# LEDSubMatrixLowDensityTHT.net
KiCad netlist of a schematic drawn in EAGLE
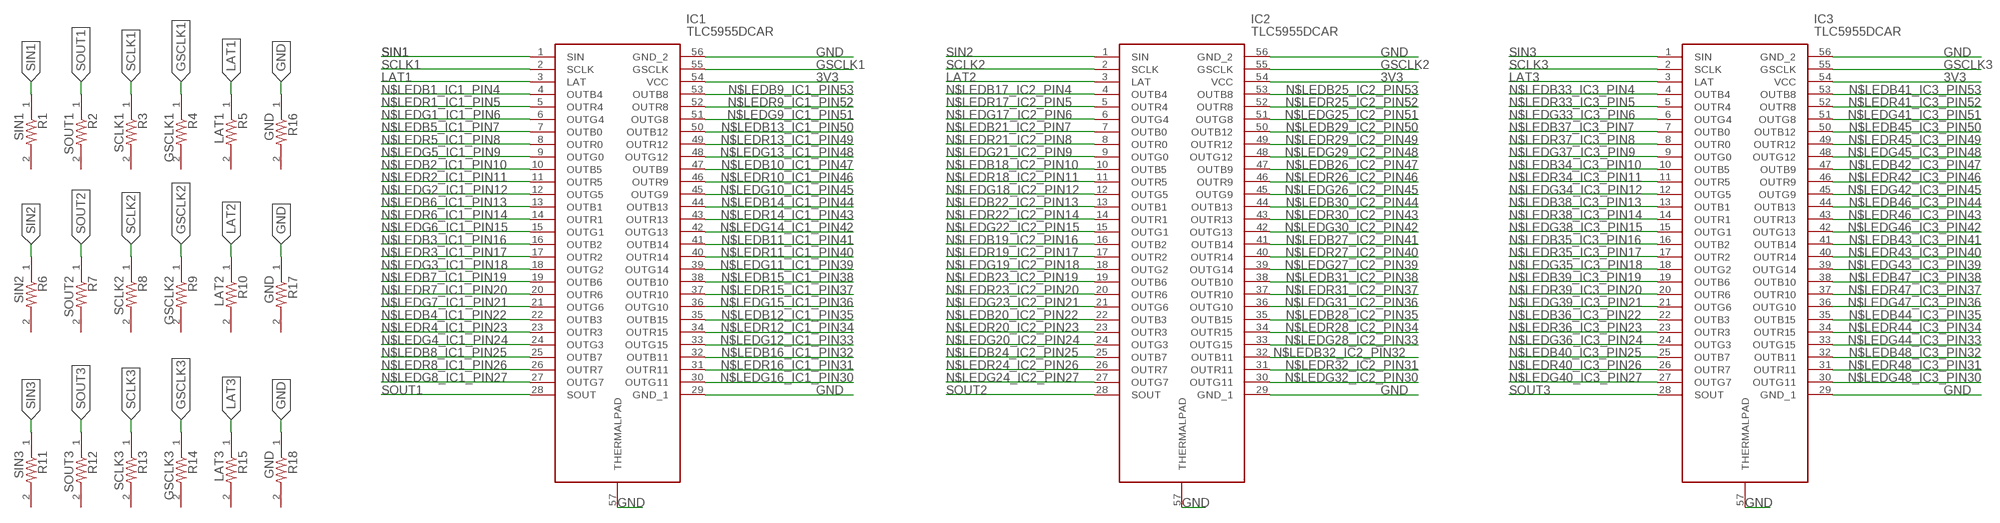
[diagram p0: schematic, sheet 1, part 1 of 2]
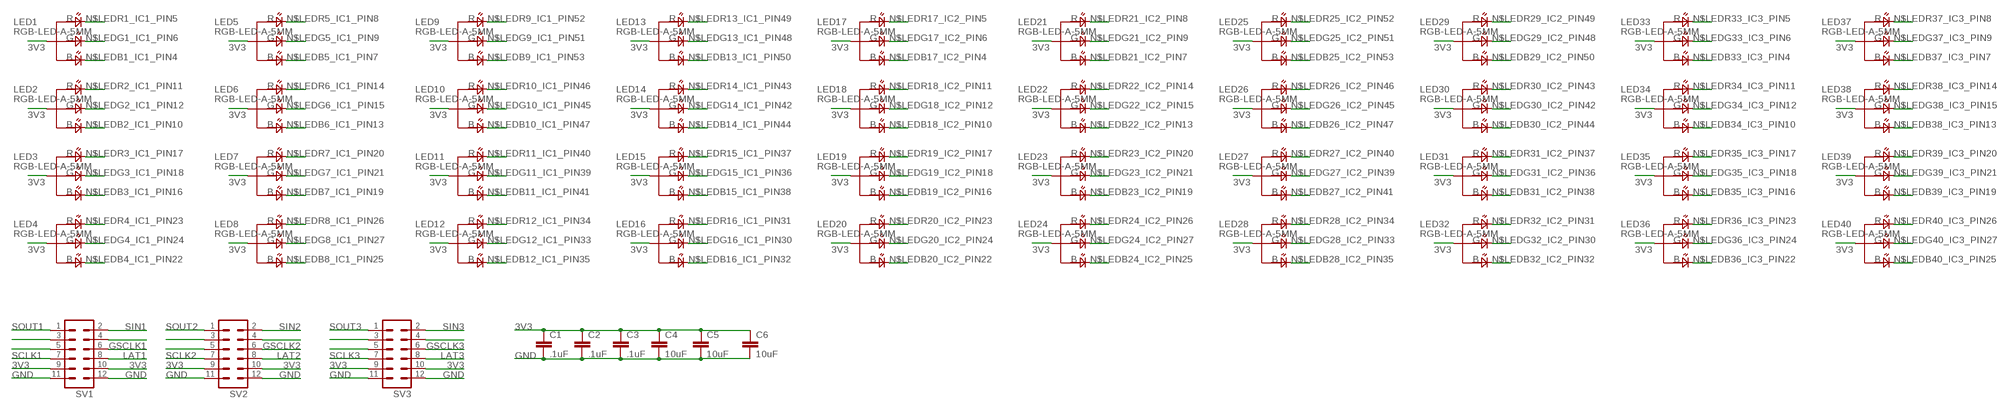
[diagram p1: schematic, sheet 1, part 2 of 2]

(export (version "E")
  (design (tool "Eeschema 10.0.6"))
  (components
    (comp (ref "C1")
      (value ".1uF")
      (footprint "eagle-import:C0603")
      (libsource (lib "eagle-import") (part "C-EUC0603"))
    )
    (comp (ref "C2")
      (value ".1uF")
      (footprint "eagle-import:C0603")
      (libsource (lib "eagle-import") (part "C-EUC0603"))
    )
    (comp (ref "C3")
      (value ".1uF")
      (footprint "eagle-import:C0603")
      (libsource (lib "eagle-import") (part "C-EUC0603"))
    )
    (comp (ref "C4")
      (value "10uF")
      (footprint "eagle-import:C0805")
      (libsource (lib "eagle-import") (part "C-EUC0805"))
    )
    (comp (ref "C5")
      (value "10uF")
      (footprint "eagle-import:C0805")
      (libsource (lib "eagle-import") (part "C-EUC0805"))
    )
    (comp (ref "C6")
      (value "10uF")
      (footprint "eagle-import:C0805")
      (libsource (lib "eagle-import") (part "C-EUC0805"))
    )
    (comp (ref "IC1")
      (value "TLC5955DCAR")
      (footprint "eagle-import:SOP50P810X120-57N")
      (fields (field (name "MOUSER_PART_NUMBER") "595-TLC5955DCAR"))
      (libsource (lib "eagle-import") (part "TLC5955DCAR"))
    )
    (comp (ref "IC2")
      (value "TLC5955DCAR")
      (footprint "eagle-import:SOP50P810X120-57N")
      (fields (field (name "MOUSER_PART_NUMBER") "595-TLC5955DCAR"))
      (libsource (lib "eagle-import") (part "TLC5955DCAR"))
    )
    (comp (ref "IC3")
      (value "TLC5955DCAR")
      (footprint "eagle-import:SOP50P810X120-57N")
      (fields (field (name "MOUSER_PART_NUMBER") "595-TLC5955DCAR"))
      (libsource (lib "eagle-import") (part "TLC5955DCAR"))
    )
    (comp (ref "LED1")
      (value "RGB-LED-A-5MM")
      (footprint "eagle-import:RGBLED-A-5MM")
      (libsource (lib "eagle-import") (part "RGB-LED-A-5MM"))
    )
    (comp (ref "LED2")
      (value "RGB-LED-A-5MM")
      (footprint "eagle-import:RGBLED-A-5MM")
      (libsource (lib "eagle-import") (part "RGB-LED-A-5MM"))
    )
    (comp (ref "LED3")
      (value "RGB-LED-A-5MM")
      (footprint "eagle-import:RGBLED-A-5MM")
      (libsource (lib "eagle-import") (part "RGB-LED-A-5MM"))
    )
    (comp (ref "LED4")
      (value "RGB-LED-A-5MM")
      (footprint "eagle-import:RGBLED-A-5MM")
      (libsource (lib "eagle-import") (part "RGB-LED-A-5MM"))
    )
    (comp (ref "LED5")
      (value "RGB-LED-A-5MM")
      (footprint "eagle-import:RGBLED-A-5MM")
      (libsource (lib "eagle-import") (part "RGB-LED-A-5MM"))
    )
    (comp (ref "LED6")
      (value "RGB-LED-A-5MM")
      (footprint "eagle-import:RGBLED-A-5MM")
      (libsource (lib "eagle-import") (part "RGB-LED-A-5MM"))
    )
    (comp (ref "LED7")
      (value "RGB-LED-A-5MM")
      (footprint "eagle-import:RGBLED-A-5MM")
      (libsource (lib "eagle-import") (part "RGB-LED-A-5MM"))
    )
    (comp (ref "LED8")
      (value "RGB-LED-A-5MM")
      (footprint "eagle-import:RGBLED-A-5MM")
      (libsource (lib "eagle-import") (part "RGB-LED-A-5MM"))
    )
    (comp (ref "LED9")
      (value "RGB-LED-A-5MM")
      (footprint "eagle-import:RGBLED-A-5MM")
      (libsource (lib "eagle-import") (part "RGB-LED-A-5MM"))
    )
    (comp (ref "LED10")
      (value "RGB-LED-A-5MM")
      (footprint "eagle-import:RGBLED-A-5MM")
      (libsource (lib "eagle-import") (part "RGB-LED-A-5MM"))
    )
    (comp (ref "LED11")
      (value "RGB-LED-A-5MM")
      (footprint "eagle-import:RGBLED-A-5MM")
      (libsource (lib "eagle-import") (part "RGB-LED-A-5MM"))
    )
    (comp (ref "LED12")
      (value "RGB-LED-A-5MM")
      (footprint "eagle-import:RGBLED-A-5MM")
      (libsource (lib "eagle-import") (part "RGB-LED-A-5MM"))
    )
    (comp (ref "LED13")
      (value "RGB-LED-A-5MM")
      (footprint "eagle-import:RGBLED-A-5MM")
      (libsource (lib "eagle-import") (part "RGB-LED-A-5MM"))
    )
    (comp (ref "LED14")
      (value "RGB-LED-A-5MM")
      (footprint "eagle-import:RGBLED-A-5MM")
      (libsource (lib "eagle-import") (part "RGB-LED-A-5MM"))
    )
    (comp (ref "LED15")
      (value "RGB-LED-A-5MM")
      (footprint "eagle-import:RGBLED-A-5MM")
      (libsource (lib "eagle-import") (part "RGB-LED-A-5MM"))
    )
    (comp (ref "LED16")
      (value "RGB-LED-A-5MM")
      (footprint "eagle-import:RGBLED-A-5MM")
      (libsource (lib "eagle-import") (part "RGB-LED-A-5MM"))
    )
    (comp (ref "LED17")
      (value "RGB-LED-A-5MM")
      (footprint "eagle-import:RGBLED-A-5MM")
      (libsource (lib "eagle-import") (part "RGB-LED-A-5MM"))
    )
    (comp (ref "LED18")
      (value "RGB-LED-A-5MM")
      (footprint "eagle-import:RGBLED-A-5MM")
      (libsource (lib "eagle-import") (part "RGB-LED-A-5MM"))
    )
    (comp (ref "LED19")
      (value "RGB-LED-A-5MM")
      (footprint "eagle-import:RGBLED-A-5MM")
      (libsource (lib "eagle-import") (part "RGB-LED-A-5MM"))
    )
    (comp (ref "LED20")
      (value "RGB-LED-A-5MM")
      (footprint "eagle-import:RGBLED-A-5MM")
      (libsource (lib "eagle-import") (part "RGB-LED-A-5MM"))
    )
    (comp (ref "LED21")
      (value "RGB-LED-A-5MM")
      (footprint "eagle-import:RGBLED-A-5MM")
      (libsource (lib "eagle-import") (part "RGB-LED-A-5MM"))
    )
    (comp (ref "LED22")
      (value "RGB-LED-A-5MM")
      (footprint "eagle-import:RGBLED-A-5MM")
      (libsource (lib "eagle-import") (part "RGB-LED-A-5MM"))
    )
    (comp (ref "LED23")
      (value "RGB-LED-A-5MM")
      (footprint "eagle-import:RGBLED-A-5MM")
      (libsource (lib "eagle-import") (part "RGB-LED-A-5MM"))
    )
    (comp (ref "LED24")
      (value "RGB-LED-A-5MM")
      (footprint "eagle-import:RGBLED-A-5MM")
      (libsource (lib "eagle-import") (part "RGB-LED-A-5MM"))
    )
    (comp (ref "LED25")
      (value "RGB-LED-A-5MM")
      (footprint "eagle-import:RGBLED-A-5MM")
      (libsource (lib "eagle-import") (part "RGB-LED-A-5MM"))
    )
    (comp (ref "LED26")
      (value "RGB-LED-A-5MM")
      (footprint "eagle-import:RGBLED-A-5MM")
      (libsource (lib "eagle-import") (part "RGB-LED-A-5MM"))
    )
    (comp (ref "LED27")
      (value "RGB-LED-A-5MM")
      (footprint "eagle-import:RGBLED-A-5MM")
      (libsource (lib "eagle-import") (part "RGB-LED-A-5MM"))
    )
    (comp (ref "LED28")
      (value "RGB-LED-A-5MM")
      (footprint "eagle-import:RGBLED-A-5MM")
      (libsource (lib "eagle-import") (part "RGB-LED-A-5MM"))
    )
    (comp (ref "LED29")
      (value "RGB-LED-A-5MM")
      (footprint "eagle-import:RGBLED-A-5MM")
      (libsource (lib "eagle-import") (part "RGB-LED-A-5MM"))
    )
    (comp (ref "LED30")
      (value "RGB-LED-A-5MM")
      (footprint "eagle-import:RGBLED-A-5MM")
      (libsource (lib "eagle-import") (part "RGB-LED-A-5MM"))
    )
    (comp (ref "LED31")
      (value "RGB-LED-A-5MM")
      (footprint "eagle-import:RGBLED-A-5MM")
      (libsource (lib "eagle-import") (part "RGB-LED-A-5MM"))
    )
    (comp (ref "LED32")
      (value "RGB-LED-A-5MM")
      (footprint "eagle-import:RGBLED-A-5MM")
      (libsource (lib "eagle-import") (part "RGB-LED-A-5MM"))
    )
    (comp (ref "LED33")
      (value "RGB-LED-A-5MM")
      (footprint "eagle-import:RGBLED-A-5MM")
      (libsource (lib "eagle-import") (part "RGB-LED-A-5MM"))
    )
    (comp (ref "LED34")
      (value "RGB-LED-A-5MM")
      (footprint "eagle-import:RGBLED-A-5MM")
      (libsource (lib "eagle-import") (part "RGB-LED-A-5MM"))
    )
    (comp (ref "LED35")
      (value "RGB-LED-A-5MM")
      (footprint "eagle-import:RGBLED-A-5MM")
      (libsource (lib "eagle-import") (part "RGB-LED-A-5MM"))
    )
    (comp (ref "LED36")
      (value "RGB-LED-A-5MM")
      (footprint "eagle-import:RGBLED-A-5MM")
      (libsource (lib "eagle-import") (part "RGB-LED-A-5MM"))
    )
    (comp (ref "LED37")
      (value "RGB-LED-A-5MM")
      (footprint "eagle-import:RGBLED-A-5MM")
      (libsource (lib "eagle-import") (part "RGB-LED-A-5MM"))
    )
    (comp (ref "LED38")
      (value "RGB-LED-A-5MM")
      (footprint "eagle-import:RGBLED-A-5MM")
      (libsource (lib "eagle-import") (part "RGB-LED-A-5MM"))
    )
    (comp (ref "LED39")
      (value "RGB-LED-A-5MM")
      (footprint "eagle-import:RGBLED-A-5MM")
      (libsource (lib "eagle-import") (part "RGB-LED-A-5MM"))
    )
    (comp (ref "LED40")
      (value "RGB-LED-A-5MM")
      (footprint "eagle-import:RGBLED-A-5MM")
      (libsource (lib "eagle-import") (part "RGB-LED-A-5MM"))
    )
    (comp (ref "R1")
      (value "SIN1")
      (footprint "eagle-import:RESC3216X70N")
      (fields
        (field (name "DIGI-KEY_PART_NUMBER") "2019-RCWCTECT-ND")
        (field (name "MF") "KOA Speer")
        (field (name "MP") "RCWCTE")
      )
      (libsource (lib "eagle-import") (part "RCWCTE"))
    )
    (comp (ref "R2")
      (value "SOUT1")
      (footprint "eagle-import:RESC3216X70N")
      (fields
        (field (name "DIGI-KEY_PART_NUMBER") "2019-RCWCTECT-ND")
        (field (name "MF") "KOA Speer")
        (field (name "MP") "RCWCTE")
      )
      (libsource (lib "eagle-import") (part "RCWCTE"))
    )
    (comp (ref "R3")
      (value "SCLK1")
      (footprint "eagle-import:RESC3216X70N")
      (fields
        (field (name "DIGI-KEY_PART_NUMBER") "2019-RCWCTECT-ND")
        (field (name "MF") "KOA Speer")
        (field (name "MP") "RCWCTE")
      )
      (libsource (lib "eagle-import") (part "RCWCTE"))
    )
    (comp (ref "R4")
      (value "GSCLK1")
      (footprint "eagle-import:RESC3216X70N")
      (fields
        (field (name "DIGI-KEY_PART_NUMBER") "2019-RCWCTECT-ND")
        (field (name "MF") "KOA Speer")
        (field (name "MP") "RCWCTE")
      )
      (libsource (lib "eagle-import") (part "RCWCTE"))
    )
    (comp (ref "R5")
      (value "LAT1")
      (footprint "eagle-import:RESC3216X70N")
      (fields
        (field (name "DIGI-KEY_PART_NUMBER") "2019-RCWCTECT-ND")
        (field (name "MF") "KOA Speer")
        (field (name "MP") "RCWCTE")
      )
      (libsource (lib "eagle-import") (part "RCWCTE"))
    )
    (comp (ref "R6")
      (value "SIN2")
      (footprint "eagle-import:RESC3216X70N")
      (fields
        (field (name "DIGI-KEY_PART_NUMBER") "2019-RCWCTECT-ND")
        (field (name "MF") "KOA Speer")
        (field (name "MP") "RCWCTE")
      )
      (libsource (lib "eagle-import") (part "RCWCTE"))
    )
    (comp (ref "R7")
      (value "SOUT2")
      (footprint "eagle-import:RESC3216X70N")
      (fields
        (field (name "DIGI-KEY_PART_NUMBER") "2019-RCWCTECT-ND")
        (field (name "MF") "KOA Speer")
        (field (name "MP") "RCWCTE")
      )
      (libsource (lib "eagle-import") (part "RCWCTE"))
    )
    (comp (ref "R8")
      (value "SCLK2")
      (footprint "eagle-import:RESC3216X70N")
      (fields
        (field (name "DIGI-KEY_PART_NUMBER") "2019-RCWCTECT-ND")
        (field (name "MF") "KOA Speer")
        (field (name "MP") "RCWCTE")
      )
      (libsource (lib "eagle-import") (part "RCWCTE"))
    )
    (comp (ref "R9")
      (value "GSCLK2")
      (footprint "eagle-import:RESC3216X70N")
      (fields
        (field (name "DIGI-KEY_PART_NUMBER") "2019-RCWCTECT-ND")
        (field (name "MF") "KOA Speer")
        (field (name "MP") "RCWCTE")
      )
      (libsource (lib "eagle-import") (part "RCWCTE"))
    )
    (comp (ref "R10")
      (value "LAT2")
      (footprint "eagle-import:RESC3216X70N")
      (fields
        (field (name "DIGI-KEY_PART_NUMBER") "2019-RCWCTECT-ND")
        (field (name "MF") "KOA Speer")
        (field (name "MP") "RCWCTE")
      )
      (libsource (lib "eagle-import") (part "RCWCTE"))
    )
    (comp (ref "R11")
      (value "SIN3")
      (footprint "eagle-import:RESC3216X70N")
      (fields
        (field (name "DIGI-KEY_PART_NUMBER") "2019-RCWCTECT-ND")
        (field (name "MF") "KOA Speer")
        (field (name "MP") "RCWCTE")
      )
      (libsource (lib "eagle-import") (part "RCWCTE"))
    )
    (comp (ref "R12")
      (value "SOUT3")
      (footprint "eagle-import:RESC3216X70N")
      (fields
        (field (name "DIGI-KEY_PART_NUMBER") "2019-RCWCTECT-ND")
        (field (name "MF") "KOA Speer")
        (field (name "MP") "RCWCTE")
      )
      (libsource (lib "eagle-import") (part "RCWCTE"))
    )
    (comp (ref "R13")
      (value "SCLK3")
      (footprint "eagle-import:RESC3216X70N")
      (fields
        (field (name "DIGI-KEY_PART_NUMBER") "2019-RCWCTECT-ND")
        (field (name "MF") "KOA Speer")
        (field (name "MP") "RCWCTE")
      )
      (libsource (lib "eagle-import") (part "RCWCTE"))
    )
    (comp (ref "R14")
      (value "GSCLK3")
      (footprint "eagle-import:RESC3216X70N")
      (fields
        (field (name "DIGI-KEY_PART_NUMBER") "2019-RCWCTECT-ND")
        (field (name "MF") "KOA Speer")
        (field (name "MP") "RCWCTE")
      )
      (libsource (lib "eagle-import") (part "RCWCTE"))
    )
    (comp (ref "R15")
      (value "LAT3")
      (footprint "eagle-import:RESC3216X70N")
      (fields
        (field (name "DIGI-KEY_PART_NUMBER") "2019-RCWCTECT-ND")
        (field (name "MF") "KOA Speer")
        (field (name "MP") "RCWCTE")
      )
      (libsource (lib "eagle-import") (part "RCWCTE"))
    )
    (comp (ref "R16")
      (value "GND")
      (footprint "eagle-import:RESC3216X70N")
      (fields
        (field (name "DIGI-KEY_PART_NUMBER") "2019-RCWCTECT-ND")
        (field (name "MF") "KOA Speer")
        (field (name "MP") "RCWCTE")
      )
      (libsource (lib "eagle-import") (part "RCWCTE"))
    )
    (comp (ref "R17")
      (value "GND")
      (footprint "eagle-import:RESC3216X70N")
      (fields
        (field (name "DIGI-KEY_PART_NUMBER") "2019-RCWCTECT-ND")
        (field (name "MF") "KOA Speer")
        (field (name "MP") "RCWCTE")
      )
      (libsource (lib "eagle-import") (part "RCWCTE"))
    )
    (comp (ref "R18")
      (value "GND")
      (footprint "eagle-import:RESC3216X70N")
      (fields
        (field (name "DIGI-KEY_PART_NUMBER") "2019-RCWCTECT-ND")
        (field (name "MF") "KOA Speer")
        (field (name "MP") "RCWCTE")
      )
      (libsource (lib "eagle-import") (part "RCWCTE"))
    )
    (comp (ref "SV1")
      (value "MA06-2")
      (footprint "eagle-import:MA06-2")
      (libsource (lib "eagle-import") (part "MA06-2"))
    )
    (comp (ref "SV2")
      (value "MA06-2")
      (footprint "eagle-import:MA06-2")
      (libsource (lib "eagle-import") (part "MA06-2"))
    )
    (comp (ref "SV3")
      (value "MA06-2")
      (footprint "eagle-import:MA06-2")
      (libsource (lib "eagle-import") (part "MA06-2"))
    )
  )
  (nets
    (net (code "1") (name "/3V3") (class "Default")
      (node (ref "C1") (pin "1") (pinfunction "1_1") (pintype "passive"))
      (node (ref "C2") (pin "1") (pinfunction "1_1") (pintype "passive"))
      (node (ref "C3") (pin "1") (pinfunction "1_1") (pintype "passive"))
      (node (ref "C4") (pin "1") (pinfunction "1_1") (pintype "passive"))
      (node (ref "C5") (pin "1") (pinfunction "1_1") (pintype "passive"))
      (node (ref "C6") (pin "1") (pinfunction "1_1") (pintype "passive"))
      (node (ref "IC1") (pin "54") (pinfunction "VCC_54") (pintype "bidirectional"))
      (node (ref "IC2") (pin "54") (pinfunction "VCC_54") (pintype "bidirectional"))
      (node (ref "IC3") (pin "54") (pinfunction "VCC_54") (pintype "bidirectional"))
      (node (ref "LED1") (pin "AN") (pinfunction "COM_AN") (pintype "bidirectional"))
      (node (ref "LED10") (pin "AN") (pinfunction "COM_AN") (pintype "bidirectional"))
      (node (ref "LED11") (pin "AN") (pinfunction "COM_AN") (pintype "bidirectional"))
      (node (ref "LED12") (pin "AN") (pinfunction "COM_AN") (pintype "bidirectional"))
      (node (ref "LED13") (pin "AN") (pinfunction "COM_AN") (pintype "bidirectional"))
      (node (ref "LED14") (pin "AN") (pinfunction "COM_AN") (pintype "bidirectional"))
      (node (ref "LED15") (pin "AN") (pinfunction "COM_AN") (pintype "bidirectional"))
      (node (ref "LED16") (pin "AN") (pinfunction "COM_AN") (pintype "bidirectional"))
      (node (ref "LED17") (pin "AN") (pinfunction "COM_AN") (pintype "bidirectional"))
      (node (ref "LED18") (pin "AN") (pinfunction "COM_AN") (pintype "bidirectional"))
      (node (ref "LED19") (pin "AN") (pinfunction "COM_AN") (pintype "bidirectional"))
      (node (ref "LED2") (pin "AN") (pinfunction "COM_AN") (pintype "bidirectional"))
      (node (ref "LED20") (pin "AN") (pinfunction "COM_AN") (pintype "bidirectional"))
      (node (ref "LED21") (pin "AN") (pinfunction "COM_AN") (pintype "bidirectional"))
      (node (ref "LED22") (pin "AN") (pinfunction "COM_AN") (pintype "bidirectional"))
      (node (ref "LED23") (pin "AN") (pinfunction "COM_AN") (pintype "bidirectional"))
      (node (ref "LED24") (pin "AN") (pinfunction "COM_AN") (pintype "bidirectional"))
      (node (ref "LED25") (pin "AN") (pinfunction "COM_AN") (pintype "bidirectional"))
      (node (ref "LED26") (pin "AN") (pinfunction "COM_AN") (pintype "bidirectional"))
      (node (ref "LED27") (pin "AN") (pinfunction "COM_AN") (pintype "bidirectional"))
      (node (ref "LED28") (pin "AN") (pinfunction "COM_AN") (pintype "bidirectional"))
      (node (ref "LED29") (pin "AN") (pinfunction "COM_AN") (pintype "bidirectional"))
      (node (ref "LED3") (pin "AN") (pinfunction "COM_AN") (pintype "bidirectional"))
      (node (ref "LED30") (pin "AN") (pinfunction "COM_AN") (pintype "bidirectional"))
      (node (ref "LED31") (pin "AN") (pinfunction "COM_AN") (pintype "bidirectional"))
      (node (ref "LED32") (pin "AN") (pinfunction "COM_AN") (pintype "bidirectional"))
      (node (ref "LED33") (pin "AN") (pinfunction "COM_AN") (pintype "bidirectional"))
      (node (ref "LED34") (pin "AN") (pinfunction "COM_AN") (pintype "bidirectional"))
      (node (ref "LED35") (pin "AN") (pinfunction "COM_AN") (pintype "bidirectional"))
      (node (ref "LED36") (pin "AN") (pinfunction "COM_AN") (pintype "bidirectional"))
      (node (ref "LED37") (pin "AN") (pinfunction "COM_AN") (pintype "bidirectional"))
      (node (ref "LED38") (pin "AN") (pinfunction "COM_AN") (pintype "bidirectional"))
      (node (ref "LED39") (pin "AN") (pinfunction "COM_AN") (pintype "bidirectional"))
      (node (ref "LED4") (pin "AN") (pinfunction "COM_AN") (pintype "bidirectional"))
      (node (ref "LED40") (pin "AN") (pinfunction "COM_AN") (pintype "bidirectional"))
      (node (ref "LED5") (pin "AN") (pinfunction "COM_AN") (pintype "bidirectional"))
      (node (ref "LED6") (pin "AN") (pinfunction "COM_AN") (pintype "bidirectional"))
      (node (ref "LED7") (pin "AN") (pinfunction "COM_AN") (pintype "bidirectional"))
      (node (ref "LED8") (pin "AN") (pinfunction "COM_AN") (pintype "bidirectional"))
      (node (ref "LED9") (pin "AN") (pinfunction "COM_AN") (pintype "bidirectional"))
      (node (ref "SV1") (pin "10") (pinfunction "10_10") (pintype "passive"))
      (node (ref "SV1") (pin "9") (pinfunction "9_9") (pintype "passive"))
      (node (ref "SV2") (pin "10") (pinfunction "10_10") (pintype "passive"))
      (node (ref "SV2") (pin "9") (pinfunction "9_9") (pintype "passive"))
      (node (ref "SV3") (pin "10") (pinfunction "10_10") (pintype "passive"))
      (node (ref "SV3") (pin "9") (pinfunction "9_9") (pintype "passive"))
    )
    (net (code "2") (name "/N$LEDB1_IC1_PIN4") (class "Default")
      (node (ref "IC1") (pin "4") (pinfunction "OUTB4_4") (pintype "bidirectional"))
      (node (ref "LED1") (pin "B") (pinfunction "BLUE_B") (pintype "bidirectional"))
    )
    (net (code "3") (name "/N$LEDB2_IC1_PIN10") (class "Default")
      (node (ref "IC1") (pin "10") (pinfunction "OUTB5_10") (pintype "bidirectional"))
      (node (ref "LED2") (pin "B") (pinfunction "BLUE_B") (pintype "bidirectional"))
    )
    (net (code "4") (name "/N$LEDB3_IC1_PIN16") (class "Default")
      (node (ref "IC1") (pin "16") (pinfunction "OUTB2_16") (pintype "bidirectional"))
      (node (ref "LED3") (pin "B") (pinfunction "BLUE_B") (pintype "bidirectional"))
    )
    (net (code "5") (name "/N$LEDB4_IC1_PIN22") (class "Default")
      (node (ref "IC1") (pin "22") (pinfunction "OUTB3_22") (pintype "bidirectional"))
      (node (ref "LED4") (pin "B") (pinfunction "BLUE_B") (pintype "bidirectional"))
    )
    (net (code "6") (name "/N$LEDB5_IC1_PIN7") (class "Default")
      (node (ref "IC1") (pin "7") (pinfunction "OUTB0_7") (pintype "bidirectional"))
      (node (ref "LED5") (pin "B") (pinfunction "BLUE_B") (pintype "bidirectional"))
    )
    (net (code "7") (name "/N$LEDB6_IC1_PIN13") (class "Default")
      (node (ref "IC1") (pin "13") (pinfunction "OUTB1_13") (pintype "bidirectional"))
      (node (ref "LED6") (pin "B") (pinfunction "BLUE_B") (pintype "bidirectional"))
    )
    (net (code "8") (name "/N$LEDB7_IC1_PIN19") (class "Default")
      (node (ref "IC1") (pin "19") (pinfunction "OUTB6_19") (pintype "bidirectional"))
      (node (ref "LED7") (pin "B") (pinfunction "BLUE_B") (pintype "bidirectional"))
    )
    (net (code "9") (name "/N$LEDB8_IC1_PIN25") (class "Default")
      (node (ref "IC1") (pin "25") (pinfunction "OUTB7_25") (pintype "bidirectional"))
      (node (ref "LED8") (pin "B") (pinfunction "BLUE_B") (pintype "bidirectional"))
    )
    (net (code "10") (name "/N$LEDB9_IC1_PIN53") (class "Default")
      (node (ref "IC1") (pin "53") (pinfunction "OUTB8_53") (pintype "bidirectional"))
      (node (ref "LED9") (pin "B") (pinfunction "BLUE_B") (pintype "bidirectional"))
    )
    (net (code "11") (name "/N$LEDB10_IC1_PIN47") (class "Default")
      (node (ref "IC1") (pin "47") (pinfunction "OUTB9_47") (pintype "bidirectional"))
      (node (ref "LED10") (pin "B") (pinfunction "BLUE_B") (pintype "bidirectional"))
    )
    (net (code "12") (name "/N$LEDB11_IC1_PIN41") (class "Default")
      (node (ref "IC1") (pin "41") (pinfunction "OUTB14_41") (pintype "bidirectional"))
      (node (ref "LED11") (pin "B") (pinfunction "BLUE_B") (pintype "bidirectional"))
    )
    (net (code "13") (name "/N$LEDB12_IC1_PIN35") (class "Default")
      (node (ref "IC1") (pin "35") (pinfunction "OUTB15_35") (pintype "bidirectional"))
      (node (ref "LED12") (pin "B") (pinfunction "BLUE_B") (pintype "bidirectional"))
    )
    (net (code "14") (name "/N$LEDB13_IC1_PIN50") (class "Default")
      (node (ref "IC1") (pin "50") (pinfunction "OUTB12_50") (pintype "bidirectional"))
      (node (ref "LED13") (pin "B") (pinfunction "BLUE_B") (pintype "bidirectional"))
    )
    (net (code "15") (name "/N$LEDB14_IC1_PIN44") (class "Default")
      (node (ref "IC1") (pin "44") (pinfunction "OUTB13_44") (pintype "bidirectional"))
      (node (ref "LED14") (pin "B") (pinfunction "BLUE_B") (pintype "bidirectional"))
    )
    (net (code "16") (name "/N$LEDB15_IC1_PIN38") (class "Default")
      (node (ref "IC1") (pin "38") (pinfunction "OUTB10_38") (pintype "bidirectional"))
      (node (ref "LED15") (pin "B") (pinfunction "BLUE_B") (pintype "bidirectional"))
    )
    (net (code "17") (name "/N$LEDB16_IC1_PIN32") (class "Default")
      (node (ref "IC1") (pin "32") (pinfunction "OUTB11_32") (pintype "bidirectional"))
      (node (ref "LED16") (pin "B") (pinfunction "BLUE_B") (pintype "bidirectional"))
    )
    (net (code "18") (name "/N$LEDB17_IC2_PIN4") (class "Default")
      (node (ref "IC2") (pin "4") (pinfunction "OUTB4_4") (pintype "bidirectional"))
      (node (ref "LED17") (pin "B") (pinfunction "BLUE_B") (pintype "bidirectional"))
    )
    (net (code "19") (name "/N$LEDB18_IC2_PIN10") (class "Default")
      (node (ref "IC2") (pin "10") (pinfunction "OUTB5_10") (pintype "bidirectional"))
      (node (ref "LED18") (pin "B") (pinfunction "BLUE_B") (pintype "bidirectional"))
    )
    (net (code "20") (name "/N$LEDB19_IC2_PIN16") (class "Default")
      (node (ref "IC2") (pin "16") (pinfunction "OUTB2_16") (pintype "bidirectional"))
      (node (ref "LED19") (pin "B") (pinfunction "BLUE_B") (pintype "bidirectional"))
    )
    (net (code "21") (name "/N$LEDB20_IC2_PIN22") (class "Default")
      (node (ref "IC2") (pin "22") (pinfunction "OUTB3_22") (pintype "bidirectional"))
      (node (ref "LED20") (pin "B") (pinfunction "BLUE_B") (pintype "bidirectional"))
    )
    (net (code "22") (name "/N$LEDB21_IC2_PIN7") (class "Default")
      (node (ref "IC2") (pin "7") (pinfunction "OUTB0_7") (pintype "bidirectional"))
      (node (ref "LED21") (pin "B") (pinfunction "BLUE_B") (pintype "bidirectional"))
    )
    (net (code "23") (name "/N$LEDB22_IC2_PIN13") (class "Default")
      (node (ref "IC2") (pin "13") (pinfunction "OUTB1_13") (pintype "bidirectional"))
      (node (ref "LED22") (pin "B") (pinfunction "BLUE_B") (pintype "bidirectional"))
    )
    (net (code "24") (name "/N$LEDB23_IC2_PIN19") (class "Default")
      (node (ref "IC2") (pin "19") (pinfunction "OUTB6_19") (pintype "bidirectional"))
      (node (ref "LED23") (pin "B") (pinfunction "BLUE_B") (pintype "bidirectional"))
    )
    (net (code "25") (name "/N$LEDB24_IC2_PIN25") (class "Default")
      (node (ref "IC2") (pin "25") (pinfunction "OUTB7_25") (pintype "bidirectional"))
      (node (ref "LED24") (pin "B") (pinfunction "BLUE_B") (pintype "bidirectional"))
    )
    (net (code "26") (name "/N$LEDB25_IC2_PIN53") (class "Default")
      (node (ref "IC2") (pin "53") (pinfunction "OUTB8_53") (pintype "bidirectional"))
      (node (ref "LED25") (pin "B") (pinfunction "BLUE_B") (pintype "bidirectional"))
    )
    (net (code "27") (name "/N$LEDB26_IC2_PIN47") (class "Default")
      (node (ref "IC2") (pin "47") (pinfunction "OUTB9_47") (pintype "bidirectional"))
      (node (ref "LED26") (pin "B") (pinfunction "BLUE_B") (pintype "bidirectional"))
    )
    (net (code "28") (name "/N$LEDB27_IC2_PIN41") (class "Default")
      (node (ref "IC2") (pin "41") (pinfunction "OUTB14_41") (pintype "bidirectional"))
      (node (ref "LED27") (pin "B") (pinfunction "BLUE_B") (pintype "bidirectional"))
    )
    (net (code "29") (name "/N$LEDB28_IC2_PIN35") (class "Default")
      (node (ref "IC2") (pin "35") (pinfunction "OUTB15_35") (pintype "bidirectional"))
      (node (ref "LED28") (pin "B") (pinfunction "BLUE_B") (pintype "bidirectional"))
    )
    (net (code "30") (name "/N$LEDB29_IC2_PIN50") (class "Default")
      (node (ref "IC2") (pin "50") (pinfunction "OUTB12_50") (pintype "bidirectional"))
      (node (ref "LED29") (pin "B") (pinfunction "BLUE_B") (pintype "bidirectional"))
    )
    (net (code "31") (name "/N$LEDB30_IC2_PIN44") (class "Default")
      (node (ref "IC2") (pin "44") (pinfunction "OUTB13_44") (pintype "bidirectional"))
      (node (ref "LED30") (pin "B") (pinfunction "BLUE_B") (pintype "bidirectional"))
    )
    (net (code "32") (name "/N$LEDB31_IC2_PIN38") (class "Default")
      (node (ref "IC2") (pin "38") (pinfunction "OUTB10_38") (pintype "bidirectional"))
      (node (ref "LED31") (pin "B") (pinfunction "BLUE_B") (pintype "bidirectional"))
    )
    (net (code "33") (name "/N$LEDB32_IC2_PIN32") (class "Default")
      (node (ref "IC2") (pin "32") (pinfunction "OUTB11_32") (pintype "bidirectional"))
      (node (ref "LED32") (pin "B") (pinfunction "BLUE_B") (pintype "bidirectional"))
    )
    (net (code "34") (name "/N$LEDB33_IC3_PIN4") (class "Default")
      (node (ref "IC3") (pin "4") (pinfunction "OUTB4_4") (pintype "bidirectional"))
      (node (ref "LED33") (pin "B") (pinfunction "BLUE_B") (pintype "bidirectional"))
    )
    (net (code "35") (name "/N$LEDB34_IC3_PIN10") (class "Default")
      (node (ref "IC3") (pin "10") (pinfunction "OUTB5_10") (pintype "bidirectional"))
      (node (ref "LED34") (pin "B") (pinfunction "BLUE_B") (pintype "bidirectional"))
    )
    (net (code "36") (name "/N$LEDB35_IC3_PIN16") (class "Default")
      (node (ref "IC3") (pin "16") (pinfunction "OUTB2_16") (pintype "bidirectional"))
      (node (ref "LED35") (pin "B") (pinfunction "BLUE_B") (pintype "bidirectional"))
    )
    (net (code "37") (name "/N$LEDB36_IC3_PIN22") (class "Default")
      (node (ref "IC3") (pin "22") (pinfunction "OUTB3_22") (pintype "bidirectional"))
      (node (ref "LED36") (pin "B") (pinfunction "BLUE_B") (pintype "bidirectional"))
    )
    (net (code "38") (name "/N$LEDB37_IC3_PIN7") (class "Default")
      (node (ref "IC3") (pin "7") (pinfunction "OUTB0_7") (pintype "bidirectional"))
      (node (ref "LED37") (pin "B") (pinfunction "BLUE_B") (pintype "bidirectional"))
    )
    (net (code "39") (name "/N$LEDB38_IC3_PIN13") (class "Default")
      (node (ref "IC3") (pin "13") (pinfunction "OUTB1_13") (pintype "bidirectional"))
      (node (ref "LED38") (pin "B") (pinfunction "BLUE_B") (pintype "bidirectional"))
    )
    (net (code "40") (name "/N$LEDB39_IC3_PIN19") (class "Default")
      (node (ref "IC3") (pin "19") (pinfunction "OUTB6_19") (pintype "bidirectional"))
      (node (ref "LED39") (pin "B") (pinfunction "BLUE_B") (pintype "bidirectional"))
    )
    (net (code "41") (name "/N$LEDB40_IC3_PIN25") (class "Default")
      (node (ref "IC3") (pin "25") (pinfunction "OUTB7_25") (pintype "bidirectional"))
      (node (ref "LED40") (pin "B") (pinfunction "BLUE_B") (pintype "bidirectional"))
    )
    (net (code "42") (name "/N$LEDB41_IC3_PIN53") (class "Default")
      (node (ref "IC3") (pin "53") (pinfunction "OUTB8_53") (pintype "bidirectional"))
    )
    (net (code "43") (name "/N$LEDB42_IC3_PIN47") (class "Default")
      (node (ref "IC3") (pin "47") (pinfunction "OUTB9_47") (pintype "bidirectional"))
    )
    (net (code "44") (name "/N$LEDB43_IC3_PIN41") (class "Default")
      (node (ref "IC3") (pin "41") (pinfunction "OUTB14_41") (pintype "bidirectional"))
    )
    (net (code "45") (name "/N$LEDB44_IC3_PIN35") (class "Default")
      (node (ref "IC3") (pin "35") (pinfunction "OUTB15_35") (pintype "bidirectional"))
    )
    (net (code "46") (name "/N$LEDB45_IC3_PIN50") (class "Default")
      (node (ref "IC3") (pin "50") (pinfunction "OUTB12_50") (pintype "bidirectional"))
    )
    (net (code "47") (name "/N$LEDB46_IC3_PIN44") (class "Default")
      (node (ref "IC3") (pin "44") (pinfunction "OUTB13_44") (pintype "bidirectional"))
    )
    (net (code "48") (name "/N$LEDB47_IC3_PIN38") (class "Default")
      (node (ref "IC3") (pin "38") (pinfunction "OUTB10_38") (pintype "bidirectional"))
    )
    (net (code "49") (name "/N$LEDB48_IC3_PIN32") (class "Default")
      (node (ref "IC3") (pin "32") (pinfunction "OUTB11_32") (pintype "bidirectional"))
    )
    (net (code "50") (name "/N$LEDG1_IC1_PIN6") (class "Default")
      (node (ref "IC1") (pin "6") (pinfunction "OUTG4_6") (pintype "bidirectional"))
      (node (ref "LED1") (pin "G") (pinfunction "GREEN_G") (pintype "bidirectional"))
    )
    (net (code "51") (name "/N$LEDG2_IC1_PIN12") (class "Default")
      (node (ref "IC1") (pin "12") (pinfunction "OUTG5_12") (pintype "bidirectional"))
      (node (ref "LED2") (pin "G") (pinfunction "GREEN_G") (pintype "bidirectional"))
    )
    (net (code "52") (name "/N$LEDG3_IC1_PIN18") (class "Default")
      (node (ref "IC1") (pin "18") (pinfunction "OUTG2_18") (pintype "bidirectional"))
      (node (ref "LED3") (pin "G") (pinfunction "GREEN_G") (pintype "bidirectional"))
    )
    (net (code "53") (name "/N$LEDG4_IC1_PIN24") (class "Default")
      (node (ref "IC1") (pin "24") (pinfunction "OUTG3_24") (pintype "bidirectional"))
      (node (ref "LED4") (pin "G") (pinfunction "GREEN_G") (pintype "bidirectional"))
    )
    (net (code "54") (name "/N$LEDG5_IC1_PIN9") (class "Default")
      (node (ref "IC1") (pin "9") (pinfunction "OUTG0_9") (pintype "bidirectional"))
      (node (ref "LED5") (pin "G") (pinfunction "GREEN_G") (pintype "bidirectional"))
    )
    (net (code "55") (name "/N$LEDG6_IC1_PIN15") (class "Default")
      (node (ref "IC1") (pin "15") (pinfunction "OUTG1_15") (pintype "bidirectional"))
      (node (ref "LED6") (pin "G") (pinfunction "GREEN_G") (pintype "bidirectional"))
    )
    (net (code "56") (name "/N$LEDG7_IC1_PIN21") (class "Default")
      (node (ref "IC1") (pin "21") (pinfunction "OUTG6_21") (pintype "bidirectional"))
      (node (ref "LED7") (pin "G") (pinfunction "GREEN_G") (pintype "bidirectional"))
    )
    (net (code "57") (name "/N$LEDG8_IC1_PIN27") (class "Default")
      (node (ref "IC1") (pin "27") (pinfunction "OUTG7_27") (pintype "bidirectional"))
      (node (ref "LED8") (pin "G") (pinfunction "GREEN_G") (pintype "bidirectional"))
    )
    (net (code "58") (name "/N$LEDG9_IC1_PIN51") (class "Default")
      (node (ref "IC1") (pin "51") (pinfunction "OUTG8_51") (pintype "bidirectional"))
      (node (ref "LED9") (pin "G") (pinfunction "GREEN_G") (pintype "bidirectional"))
    )
    (net (code "59") (name "/N$LEDG10_IC1_PIN45") (class "Default")
      (node (ref "IC1") (pin "45") (pinfunction "OUTG9_45") (pintype "bidirectional"))
      (node (ref "LED10") (pin "G") (pinfunction "GREEN_G") (pintype "bidirectional"))
    )
    (net (code "60") (name "/N$LEDG11_IC1_PIN39") (class "Default")
      (node (ref "IC1") (pin "39") (pinfunction "OUTG14_39") (pintype "bidirectional"))
      (node (ref "LED11") (pin "G") (pinfunction "GREEN_G") (pintype "bidirectional"))
    )
    (net (code "61") (name "/N$LEDG12_IC1_PIN33") (class "Default")
      (node (ref "IC1") (pin "33") (pinfunction "OUTG15_33") (pintype "bidirectional"))
      (node (ref "LED12") (pin "G") (pinfunction "GREEN_G") (pintype "bidirectional"))
    )
    (net (code "62") (name "/N$LEDG13_IC1_PIN48") (class "Default")
      (node (ref "IC1") (pin "48") (pinfunction "OUTG12_48") (pintype "bidirectional"))
      (node (ref "LED13") (pin "G") (pinfunction "GREEN_G") (pintype "bidirectional"))
    )
    (net (code "63") (name "/N$LEDG14_IC1_PIN42") (class "Default")
      (node (ref "IC1") (pin "42") (pinfunction "OUTG13_42") (pintype "bidirectional"))
      (node (ref "LED14") (pin "G") (pinfunction "GREEN_G") (pintype "bidirectional"))
    )
    (net (code "64") (name "/N$LEDG15_IC1_PIN36") (class "Default")
      (node (ref "IC1") (pin "36") (pinfunction "OUTG10_36") (pintype "bidirectional"))
      (node (ref "LED15") (pin "G") (pinfunction "GREEN_G") (pintype "bidirectional"))
    )
    (net (code "65") (name "/N$LEDG16_IC1_PIN30") (class "Default")
      (node (ref "IC1") (pin "30") (pinfunction "OUTG11_30") (pintype "bidirectional"))
      (node (ref "LED16") (pin "G") (pinfunction "GREEN_G") (pintype "bidirectional"))
    )
    (net (code "66") (name "/N$LEDG17_IC2_PIN6") (class "Default")
      (node (ref "IC2") (pin "6") (pinfunction "OUTG4_6") (pintype "bidirectional"))
      (node (ref "LED17") (pin "G") (pinfunction "GREEN_G") (pintype "bidirectional"))
    )
    (net (code "67") (name "/N$LEDG18_IC2_PIN12") (class "Default")
      (node (ref "IC2") (pin "12") (pinfunction "OUTG5_12") (pintype "bidirectional"))
      (node (ref "LED18") (pin "G") (pinfunction "GREEN_G") (pintype "bidirectional"))
    )
    (net (code "68") (name "/N$LEDG19_IC2_PIN18") (class "Default")
      (node (ref "IC2") (pin "18") (pinfunction "OUTG2_18") (pintype "bidirectional"))
      (node (ref "LED19") (pin "G") (pinfunction "GREEN_G") (pintype "bidirectional"))
    )
    (net (code "69") (name "/N$LEDG20_IC2_PIN24") (class "Default")
      (node (ref "IC2") (pin "24") (pinfunction "OUTG3_24") (pintype "bidirectional"))
      (node (ref "LED20") (pin "G") (pinfunction "GREEN_G") (pintype "bidirectional"))
    )
    (net (code "70") (name "/N$LEDG21_IC2_PIN9") (class "Default")
      (node (ref "IC2") (pin "9") (pinfunction "OUTG0_9") (pintype "bidirectional"))
      (node (ref "LED21") (pin "G") (pinfunction "GREEN_G") (pintype "bidirectional"))
    )
    (net (code "71") (name "/N$LEDG22_IC2_PIN15") (class "Default")
      (node (ref "IC2") (pin "15") (pinfunction "OUTG1_15") (pintype "bidirectional"))
      (node (ref "LED22") (pin "G") (pinfunction "GREEN_G") (pintype "bidirectional"))
    )
    (net (code "72") (name "/N$LEDG23_IC2_PIN21") (class "Default")
      (node (ref "IC2") (pin "21") (pinfunction "OUTG6_21") (pintype "bidirectional"))
      (node (ref "LED23") (pin "G") (pinfunction "GREEN_G") (pintype "bidirectional"))
    )
    (net (code "73") (name "/N$LEDG24_IC2_PIN27") (class "Default")
      (node (ref "IC2") (pin "27") (pinfunction "OUTG7_27") (pintype "bidirectional"))
      (node (ref "LED24") (pin "G") (pinfunction "GREEN_G") (pintype "bidirectional"))
    )
    (net (code "74") (name "/N$LEDG25_IC2_PIN51") (class "Default")
      (node (ref "IC2") (pin "51") (pinfunction "OUTG8_51") (pintype "bidirectional"))
      (node (ref "LED25") (pin "G") (pinfunction "GREEN_G") (pintype "bidirectional"))
    )
    (net (code "75") (name "/N$LEDG26_IC2_PIN45") (class "Default")
      (node (ref "IC2") (pin "45") (pinfunction "OUTG9_45") (pintype "bidirectional"))
      (node (ref "LED26") (pin "G") (pinfunction "GREEN_G") (pintype "bidirectional"))
    )
    (net (code "76") (name "/N$LEDG27_IC2_PIN39") (class "Default")
      (node (ref "IC2") (pin "39") (pinfunction "OUTG14_39") (pintype "bidirectional"))
      (node (ref "LED27") (pin "G") (pinfunction "GREEN_G") (pintype "bidirectional"))
    )
    (net (code "77") (name "/N$LEDG28_IC2_PIN33") (class "Default")
      (node (ref "IC2") (pin "33") (pinfunction "OUTG15_33") (pintype "bidirectional"))
      (node (ref "LED28") (pin "G") (pinfunction "GREEN_G") (pintype "bidirectional"))
    )
    (net (code "78") (name "/N$LEDG29_IC2_PIN48") (class "Default")
      (node (ref "IC2") (pin "48") (pinfunction "OUTG12_48") (pintype "bidirectional"))
      (node (ref "LED29") (pin "G") (pinfunction "GREEN_G") (pintype "bidirectional"))
    )
    (net (code "79") (name "/N$LEDG30_IC2_PIN42") (class "Default")
      (node (ref "IC2") (pin "42") (pinfunction "OUTG13_42") (pintype "bidirectional"))
      (node (ref "LED30") (pin "G") (pinfunction "GREEN_G") (pintype "bidirectional"))
    )
    (net (code "80") (name "/N$LEDG31_IC2_PIN36") (class "Default")
      (node (ref "IC2") (pin "36") (pinfunction "OUTG10_36") (pintype "bidirectional"))
      (node (ref "LED31") (pin "G") (pinfunction "GREEN_G") (pintype "bidirectional"))
    )
    (net (code "81") (name "/N$LEDG32_IC2_PIN30") (class "Default")
      (node (ref "IC2") (pin "30") (pinfunction "OUTG11_30") (pintype "bidirectional"))
      (node (ref "LED32") (pin "G") (pinfunction "GREEN_G") (pintype "bidirectional"))
    )
    (net (code "82") (name "/N$LEDG33_IC3_PIN6") (class "Default")
      (node (ref "IC3") (pin "6") (pinfunction "OUTG4_6") (pintype "bidirectional"))
      (node (ref "LED33") (pin "G") (pinfunction "GREEN_G") (pintype "bidirectional"))
    )
    (net (code "83") (name "/N$LEDG34_IC3_PIN12") (class "Default")
      (node (ref "IC3") (pin "12") (pinfunction "OUTG5_12") (pintype "bidirectional"))
      (node (ref "LED34") (pin "G") (pinfunction "GREEN_G") (pintype "bidirectional"))
    )
    (net (code "84") (name "/N$LEDG35_IC3_PIN18") (class "Default")
      (node (ref "IC3") (pin "18") (pinfunction "OUTG2_18") (pintype "bidirectional"))
      (node (ref "LED35") (pin "G") (pinfunction "GREEN_G") (pintype "bidirectional"))
    )
    (net (code "85") (name "/N$LEDG36_IC3_PIN24") (class "Default")
      (node (ref "IC3") (pin "24") (pinfunction "OUTG3_24") (pintype "bidirectional"))
      (node (ref "LED36") (pin "G") (pinfunction "GREEN_G") (pintype "bidirectional"))
    )
    (net (code "86") (name "/N$LEDG37_IC3_PIN9") (class "Default")
      (node (ref "IC3") (pin "9") (pinfunction "OUTG0_9") (pintype "bidirectional"))
      (node (ref "LED37") (pin "G") (pinfunction "GREEN_G") (pintype "bidirectional"))
    )
    (net (code "87") (name "/N$LEDG38_IC3_PIN15") (class "Default")
      (node (ref "IC3") (pin "15") (pinfunction "OUTG1_15") (pintype "bidirectional"))
      (node (ref "LED38") (pin "G") (pinfunction "GREEN_G") (pintype "bidirectional"))
    )
    (net (code "88") (name "/N$LEDG39_IC3_PIN21") (class "Default")
      (node (ref "IC3") (pin "21") (pinfunction "OUTG6_21") (pintype "bidirectional"))
      (node (ref "LED39") (pin "G") (pinfunction "GREEN_G") (pintype "bidirectional"))
    )
    (net (code "89") (name "/N$LEDG40_IC3_PIN27") (class "Default")
      (node (ref "IC3") (pin "27") (pinfunction "OUTG7_27") (pintype "bidirectional"))
      (node (ref "LED40") (pin "G") (pinfunction "GREEN_G") (pintype "bidirectional"))
    )
    (net (code "90") (name "/N$LEDG41_IC3_PIN51") (class "Default")
      (node (ref "IC3") (pin "51") (pinfunction "OUTG8_51") (pintype "bidirectional"))
    )
    (net (code "91") (name "/N$LEDG42_IC3_PIN45") (class "Default")
      (node (ref "IC3") (pin "45") (pinfunction "OUTG9_45") (pintype "bidirectional"))
    )
    (net (code "92") (name "/N$LEDG43_IC3_PIN39") (class "Default")
      (node (ref "IC3") (pin "39") (pinfunction "OUTG14_39") (pintype "bidirectional"))
    )
    (net (code "93") (name "/N$LEDG44_IC3_PIN33") (class "Default")
      (node (ref "IC3") (pin "33") (pinfunction "OUTG15_33") (pintype "bidirectional"))
    )
    (net (code "94") (name "/N$LEDG45_IC3_PIN48") (class "Default")
      (node (ref "IC3") (pin "48") (pinfunction "OUTG12_48") (pintype "bidirectional"))
    )
    (net (code "95") (name "/N$LEDG46_IC3_PIN42") (class "Default")
      (node (ref "IC3") (pin "42") (pinfunction "OUTG13_42") (pintype "bidirectional"))
    )
    (net (code "96") (name "/N$LEDG47_IC3_PIN36") (class "Default")
      (node (ref "IC3") (pin "36") (pinfunction "OUTG10_36") (pintype "bidirectional"))
    )
    (net (code "97") (name "/N$LEDG48_IC3_PIN30") (class "Default")
      (node (ref "IC3") (pin "30") (pinfunction "OUTG11_30") (pintype "bidirectional"))
    )
    (net (code "98") (name "/N$LEDR1_IC1_PIN5") (class "Default")
      (node (ref "IC1") (pin "5") (pinfunction "OUTR4_5") (pintype "bidirectional"))
      (node (ref "LED1") (pin "R") (pinfunction "RED_R") (pintype "bidirectional"))
    )
    (net (code "99") (name "/N$LEDR2_IC1_PIN11") (class "Default")
      (node (ref "IC1") (pin "11") (pinfunction "OUTR5_11") (pintype "bidirectional"))
      (node (ref "LED2") (pin "R") (pinfunction "RED_R") (pintype "bidirectional"))
    )
    (net (code "100") (name "/N$LEDR3_IC1_PIN17") (class "Default")
      (node (ref "IC1") (pin "17") (pinfunction "OUTR2_17") (pintype "bidirectional"))
      (node (ref "LED3") (pin "R") (pinfunction "RED_R") (pintype "bidirectional"))
    )
    (net (code "101") (name "/N$LEDR4_IC1_PIN23") (class "Default")
      (node (ref "IC1") (pin "23") (pinfunction "OUTR3_23") (pintype "bidirectional"))
      (node (ref "LED4") (pin "R") (pinfunction "RED_R") (pintype "bidirectional"))
    )
    (net (code "102") (name "/N$LEDR5_IC1_PIN8") (class "Default")
      (node (ref "IC1") (pin "8") (pinfunction "OUTR0_8") (pintype "bidirectional"))
      (node (ref "LED5") (pin "R") (pinfunction "RED_R") (pintype "bidirectional"))
    )
    (net (code "103") (name "/N$LEDR6_IC1_PIN14") (class "Default")
      (node (ref "IC1") (pin "14") (pinfunction "OUTR1_14") (pintype "bidirectional"))
      (node (ref "LED6") (pin "R") (pinfunction "RED_R") (pintype "bidirectional"))
    )
    (net (code "104") (name "/N$LEDR7_IC1_PIN20") (class "Default")
      (node (ref "IC1") (pin "20") (pinfunction "OUTR6_20") (pintype "bidirectional"))
      (node (ref "LED7") (pin "R") (pinfunction "RED_R") (pintype "bidirectional"))
    )
    (net (code "105") (name "/N$LEDR8_IC1_PIN26") (class "Default")
      (node (ref "IC1") (pin "26") (pinfunction "OUTR7_26") (pintype "bidirectional"))
      (node (ref "LED8") (pin "R") (pinfunction "RED_R") (pintype "bidirectional"))
    )
    (net (code "106") (name "/N$LEDR9_IC1_PIN52") (class "Default")
      (node (ref "IC1") (pin "52") (pinfunction "OUTR8_52") (pintype "bidirectional"))
      (node (ref "LED9") (pin "R") (pinfunction "RED_R") (pintype "bidirectional"))
    )
    (net (code "107") (name "/N$LEDR10_IC1_PIN46") (class "Default")
      (node (ref "IC1") (pin "46") (pinfunction "OUTR9_46") (pintype "bidirectional"))
      (node (ref "LED10") (pin "R") (pinfunction "RED_R") (pintype "bidirectional"))
    )
    (net (code "108") (name "/N$LEDR11_IC1_PIN40") (class "Default")
      (node (ref "IC1") (pin "40") (pinfunction "OUTR14_40") (pintype "bidirectional"))
      (node (ref "LED11") (pin "R") (pinfunction "RED_R") (pintype "bidirectional"))
    )
    (net (code "109") (name "/N$LEDR12_IC1_PIN34") (class "Default")
      (node (ref "IC1") (pin "34") (pinfunction "OUTR15_34") (pintype "bidirectional"))
      (node (ref "LED12") (pin "R") (pinfunction "RED_R") (pintype "bidirectional"))
    )
    (net (code "110") (name "/N$LEDR13_IC1_PIN49") (class "Default")
      (node (ref "IC1") (pin "49") (pinfunction "OUTR12_49") (pintype "bidirectional"))
      (node (ref "LED13") (pin "R") (pinfunction "RED_R") (pintype "bidirectional"))
    )
    (net (code "111") (name "/N$LEDR14_IC1_PIN43") (class "Default")
      (node (ref "IC1") (pin "43") (pinfunction "OUTR13_43") (pintype "bidirectional"))
      (node (ref "LED14") (pin "R") (pinfunction "RED_R") (pintype "bidirectional"))
    )
    (net (code "112") (name "/N$LEDR15_IC1_PIN37") (class "Default")
      (node (ref "IC1") (pin "37") (pinfunction "OUTR10_37") (pintype "bidirectional"))
      (node (ref "LED15") (pin "R") (pinfunction "RED_R") (pintype "bidirectional"))
    )
    (net (code "113") (name "/N$LEDR16_IC1_PIN31") (class "Default")
      (node (ref "IC1") (pin "31") (pinfunction "OUTR11_31") (pintype "bidirectional"))
      (node (ref "LED16") (pin "R") (pinfunction "RED_R") (pintype "bidirectional"))
    )
    (net (code "114") (name "/N$LEDR17_IC2_PIN5") (class "Default")
      (node (ref "IC2") (pin "5") (pinfunction "OUTR4_5") (pintype "bidirectional"))
      (node (ref "LED17") (pin "R") (pinfunction "RED_R") (pintype "bidirectional"))
    )
    (net (code "115") (name "/N$LEDR18_IC2_PIN11") (class "Default")
      (node (ref "IC2") (pin "11") (pinfunction "OUTR5_11") (pintype "bidirectional"))
      (node (ref "LED18") (pin "R") (pinfunction "RED_R") (pintype "bidirectional"))
    )
    (net (code "116") (name "/N$LEDR19_IC2_PIN17") (class "Default")
      (node (ref "IC2") (pin "17") (pinfunction "OUTR2_17") (pintype "bidirectional"))
      (node (ref "LED19") (pin "R") (pinfunction "RED_R") (pintype "bidirectional"))
    )
    (net (code "117") (name "/N$LEDR20_IC2_PIN23") (class "Default")
      (node (ref "IC2") (pin "23") (pinfunction "OUTR3_23") (pintype "bidirectional"))
      (node (ref "LED20") (pin "R") (pinfunction "RED_R") (pintype "bidirectional"))
    )
    (net (code "118") (name "/N$LEDR21_IC2_PIN8") (class "Default")
      (node (ref "IC2") (pin "8") (pinfunction "OUTR0_8") (pintype "bidirectional"))
      (node (ref "LED21") (pin "R") (pinfunction "RED_R") (pintype "bidirectional"))
    )
    (net (code "119") (name "/N$LEDR22_IC2_PIN14") (class "Default")
      (node (ref "IC2") (pin "14") (pinfunction "OUTR1_14") (pintype "bidirectional"))
      (node (ref "LED22") (pin "R") (pinfunction "RED_R") (pintype "bidirectional"))
    )
    (net (code "120") (name "/N$LEDR23_IC2_PIN20") (class "Default")
      (node (ref "IC2") (pin "20") (pinfunction "OUTR6_20") (pintype "bidirectional"))
      (node (ref "LED23") (pin "R") (pinfunction "RED_R") (pintype "bidirectional"))
    )
    (net (code "121") (name "/N$LEDR24_IC2_PIN26") (class "Default")
      (node (ref "IC2") (pin "26") (pinfunction "OUTR7_26") (pintype "bidirectional"))
      (node (ref "LED24") (pin "R") (pinfunction "RED_R") (pintype "bidirectional"))
    )
    (net (code "122") (name "/N$LEDR25_IC2_PIN52") (class "Default")
      (node (ref "IC2") (pin "52") (pinfunction "OUTR8_52") (pintype "bidirectional"))
      (node (ref "LED25") (pin "R") (pinfunction "RED_R") (pintype "bidirectional"))
    )
    (net (code "123") (name "/N$LEDR26_IC2_PIN46") (class "Default")
      (node (ref "IC2") (pin "46") (pinfunction "OUTR9_46") (pintype "bidirectional"))
      (node (ref "LED26") (pin "R") (pinfunction "RED_R") (pintype "bidirectional"))
    )
    (net (code "124") (name "/N$LEDR27_IC2_PIN40") (class "Default")
      (node (ref "IC2") (pin "40") (pinfunction "OUTR14_40") (pintype "bidirectional"))
      (node (ref "LED27") (pin "R") (pinfunction "RED_R") (pintype "bidirectional"))
    )
    (net (code "125") (name "/N$LEDR28_IC2_PIN34") (class "Default")
      (node (ref "IC2") (pin "34") (pinfunction "OUTR15_34") (pintype "bidirectional"))
      (node (ref "LED28") (pin "R") (pinfunction "RED_R") (pintype "bidirectional"))
    )
    (net (code "126") (name "/N$LEDR29_IC2_PIN49") (class "Default")
      (node (ref "IC2") (pin "49") (pinfunction "OUTR12_49") (pintype "bidirectional"))
      (node (ref "LED29") (pin "R") (pinfunction "RED_R") (pintype "bidirectional"))
    )
    (net (code "127") (name "/N$LEDR30_IC2_PIN43") (class "Default")
      (node (ref "IC2") (pin "43") (pinfunction "OUTR13_43") (pintype "bidirectional"))
      (node (ref "LED30") (pin "R") (pinfunction "RED_R") (pintype "bidirectional"))
    )
    (net (code "128") (name "/N$LEDR31_IC2_PIN37") (class "Default")
      (node (ref "IC2") (pin "37") (pinfunction "OUTR10_37") (pintype "bidirectional"))
      (node (ref "LED31") (pin "R") (pinfunction "RED_R") (pintype "bidirectional"))
    )
    (net (code "129") (name "/N$LEDR32_IC2_PIN31") (class "Default")
      (node (ref "IC2") (pin "31") (pinfunction "OUTR11_31") (pintype "bidirectional"))
      (node (ref "LED32") (pin "R") (pinfunction "RED_R") (pintype "bidirectional"))
    )
    (net (code "130") (name "/N$LEDR33_IC3_PIN5") (class "Default")
      (node (ref "IC3") (pin "5") (pinfunction "OUTR4_5") (pintype "bidirectional"))
      (node (ref "LED33") (pin "R") (pinfunction "RED_R") (pintype "bidirectional"))
    )
    (net (code "131") (name "/N$LEDR34_IC3_PIN11") (class "Default")
      (node (ref "IC3") (pin "11") (pinfunction "OUTR5_11") (pintype "bidirectional"))
      (node (ref "LED34") (pin "R") (pinfunction "RED_R") (pintype "bidirectional"))
    )
    (net (code "132") (name "/N$LEDR35_IC3_PIN17") (class "Default")
      (node (ref "IC3") (pin "17") (pinfunction "OUTR2_17") (pintype "bidirectional"))
      (node (ref "LED35") (pin "R") (pinfunction "RED_R") (pintype "bidirectional"))
    )
    (net (code "133") (name "/N$LEDR36_IC3_PIN23") (class "Default")
      (node (ref "IC3") (pin "23") (pinfunction "OUTR3_23") (pintype "bidirectional"))
      (node (ref "LED36") (pin "R") (pinfunction "RED_R") (pintype "bidirectional"))
    )
    (net (code "134") (name "/N$LEDR37_IC3_PIN8") (class "Default")
      (node (ref "IC3") (pin "8") (pinfunction "OUTR0_8") (pintype "bidirectional"))
      (node (ref "LED37") (pin "R") (pinfunction "RED_R") (pintype "bidirectional"))
    )
    (net (code "135") (name "/N$LEDR38_IC3_PIN14") (class "Default")
      (node (ref "IC3") (pin "14") (pinfunction "OUTR1_14") (pintype "bidirectional"))
      (node (ref "LED38") (pin "R") (pinfunction "RED_R") (pintype "bidirectional"))
    )
    (net (code "136") (name "/N$LEDR39_IC3_PIN20") (class "Default")
      (node (ref "IC3") (pin "20") (pinfunction "OUTR6_20") (pintype "bidirectional"))
      (node (ref "LED39") (pin "R") (pinfunction "RED_R") (pintype "bidirectional"))
    )
    (net (code "137") (name "/N$LEDR40_IC3_PIN26") (class "Default")
      (node (ref "IC3") (pin "26") (pinfunction "OUTR7_26") (pintype "bidirectional"))
      (node (ref "LED40") (pin "R") (pinfunction "RED_R") (pintype "bidirectional"))
    )
    (net (code "138") (name "/N$LEDR41_IC3_PIN52") (class "Default")
      (node (ref "IC3") (pin "52") (pinfunction "OUTR8_52") (pintype "bidirectional"))
    )
    (net (code "139") (name "/N$LEDR42_IC3_PIN46") (class "Default")
      (node (ref "IC3") (pin "46") (pinfunction "OUTR9_46") (pintype "bidirectional"))
    )
    (net (code "140") (name "/N$LEDR43_IC3_PIN40") (class "Default")
      (node (ref "IC3") (pin "40") (pinfunction "OUTR14_40") (pintype "bidirectional"))
    )
    (net (code "141") (name "/N$LEDR44_IC3_PIN34") (class "Default")
      (node (ref "IC3") (pin "34") (pinfunction "OUTR15_34") (pintype "bidirectional"))
    )
    (net (code "142") (name "/N$LEDR45_IC3_PIN49") (class "Default")
      (node (ref "IC3") (pin "49") (pinfunction "OUTR12_49") (pintype "bidirectional"))
    )
    (net (code "143") (name "/N$LEDR46_IC3_PIN43") (class "Default")
      (node (ref "IC3") (pin "43") (pinfunction "OUTR13_43") (pintype "bidirectional"))
    )
    (net (code "144") (name "/N$LEDR47_IC3_PIN37") (class "Default")
      (node (ref "IC3") (pin "37") (pinfunction "OUTR10_37") (pintype "bidirectional"))
    )
    (net (code "145") (name "/N$LEDR48_IC3_PIN31") (class "Default")
      (node (ref "IC3") (pin "31") (pinfunction "OUTR11_31") (pintype "bidirectional"))
    )
    (net (code "146") (name "GND") (class "Default")
      (node (ref "C1") (pin "2") (pinfunction "2_2") (pintype "passive"))
      (node (ref "C2") (pin "2") (pinfunction "2_2") (pintype "passive"))
      (node (ref "C3") (pin "2") (pinfunction "2_2") (pintype "passive"))
      (node (ref "C4") (pin "2") (pinfunction "2_2") (pintype "passive"))
      (node (ref "C5") (pin "2") (pinfunction "2_2") (pintype "passive"))
      (node (ref "C6") (pin "2") (pinfunction "2_2") (pintype "passive"))
      (node (ref "IC1") (pin "29") (pinfunction "GND_1_29") (pintype "bidirectional"))
      (node (ref "IC1") (pin "56") (pinfunction "GND_2_56") (pintype "bidirectional"))
      (node (ref "IC1") (pin "57") (pinfunction "THERMALPAD_57") (pintype "bidirectional"))
      (node (ref "IC2") (pin "29") (pinfunction "GND_1_29") (pintype "bidirectional"))
      (node (ref "IC2") (pin "56") (pinfunction "GND_2_56") (pintype "bidirectional"))
      (node (ref "IC2") (pin "57") (pinfunction "THERMALPAD_57") (pintype "bidirectional"))
      (node (ref "IC3") (pin "29") (pinfunction "GND_1_29") (pintype "bidirectional"))
      (node (ref "IC3") (pin "56") (pinfunction "GND_2_56") (pintype "bidirectional"))
      (node (ref "IC3") (pin "57") (pinfunction "THERMALPAD_57") (pintype "bidirectional"))
      (node (ref "R16") (pin "1") (pinfunction "1_1") (pintype "passive"))
      (node (ref "R17") (pin "1") (pinfunction "1_1") (pintype "passive"))
      (node (ref "R18") (pin "1") (pinfunction "1_1") (pintype "passive"))
      (node (ref "SV1") (pin "11") (pinfunction "11_11") (pintype "passive"))
      (node (ref "SV1") (pin "12") (pinfunction "12_12") (pintype "passive"))
      (node (ref "SV2") (pin "11") (pinfunction "11_11") (pintype "passive"))
      (node (ref "SV2") (pin "12") (pinfunction "12_12") (pintype "passive"))
      (node (ref "SV3") (pin "11") (pinfunction "11_11") (pintype "passive"))
      (node (ref "SV3") (pin "12") (pinfunction "12_12") (pintype "passive"))
    )
    (net (code "147") (name "GSCLK1") (class "Default")
      (node (ref "IC1") (pin "55") (pinfunction "GSCLK_55") (pintype "bidirectional"))
      (node (ref "R4") (pin "1") (pinfunction "1_1") (pintype "passive"))
      (node (ref "SV1") (pin "6") (pinfunction "6_6") (pintype "passive"))
    )
    (net (code "148") (name "GSCLK2") (class "Default")
      (node (ref "IC2") (pin "55") (pinfunction "GSCLK_55") (pintype "bidirectional"))
      (node (ref "R9") (pin "1") (pinfunction "1_1") (pintype "passive"))
      (node (ref "SV2") (pin "6") (pinfunction "6_6") (pintype "passive"))
    )
    (net (code "149") (name "GSCLK3") (class "Default")
      (node (ref "IC3") (pin "55") (pinfunction "GSCLK_55") (pintype "bidirectional"))
      (node (ref "R14") (pin "1") (pinfunction "1_1") (pintype "passive"))
      (node (ref "SV3") (pin "6") (pinfunction "6_6") (pintype "passive"))
    )
    (net (code "150") (name "LAT1") (class "Default")
      (node (ref "IC1") (pin "3") (pinfunction "LAT_3") (pintype "bidirectional"))
      (node (ref "R5") (pin "1") (pinfunction "1_1") (pintype "passive"))
      (node (ref "SV1") (pin "8") (pinfunction "8_8") (pintype "passive"))
    )
    (net (code "151") (name "LAT2") (class "Default")
      (node (ref "IC2") (pin "3") (pinfunction "LAT_3") (pintype "bidirectional"))
      (node (ref "R10") (pin "1") (pinfunction "1_1") (pintype "passive"))
      (node (ref "SV2") (pin "8") (pinfunction "8_8") (pintype "passive"))
    )
    (net (code "152") (name "LAT3") (class "Default")
      (node (ref "IC3") (pin "3") (pinfunction "LAT_3") (pintype "bidirectional"))
      (node (ref "R15") (pin "1") (pinfunction "1_1") (pintype "passive"))
      (node (ref "SV3") (pin "8") (pinfunction "8_8") (pintype "passive"))
    )
    (net (code "153") (name "SCLK1") (class "Default")
      (node (ref "IC1") (pin "2") (pinfunction "SCLK_2") (pintype "bidirectional"))
      (node (ref "R3") (pin "1") (pinfunction "1_1") (pintype "passive"))
      (node (ref "SV1") (pin "7") (pinfunction "7_7") (pintype "passive"))
    )
    (net (code "154") (name "SCLK2") (class "Default")
      (node (ref "IC2") (pin "2") (pinfunction "SCLK_2") (pintype "bidirectional"))
      (node (ref "R8") (pin "1") (pinfunction "1_1") (pintype "passive"))
      (node (ref "SV2") (pin "7") (pinfunction "7_7") (pintype "passive"))
    )
    (net (code "155") (name "SCLK3") (class "Default")
      (node (ref "IC3") (pin "2") (pinfunction "SCLK_2") (pintype "bidirectional"))
      (node (ref "R13") (pin "1") (pinfunction "1_1") (pintype "passive"))
      (node (ref "SV3") (pin "7") (pinfunction "7_7") (pintype "passive"))
    )
    (net (code "156") (name "SIN1") (class "Default")
      (node (ref "IC1") (pin "1") (pinfunction "SIN_1") (pintype "bidirectional"))
      (node (ref "R1") (pin "1") (pinfunction "1_1") (pintype "passive"))
      (node (ref "SV1") (pin "2") (pinfunction "2_2") (pintype "passive"))
    )
    (net (code "157") (name "SIN2") (class "Default")
      (node (ref "IC2") (pin "1") (pinfunction "SIN_1") (pintype "bidirectional"))
      (node (ref "R6") (pin "1") (pinfunction "1_1") (pintype "passive"))
      (node (ref "SV2") (pin "2") (pinfunction "2_2") (pintype "passive"))
    )
    (net (code "158") (name "SIN3") (class "Default")
      (node (ref "IC3") (pin "1") (pinfunction "SIN_1") (pintype "bidirectional"))
      (node (ref "R11") (pin "1") (pinfunction "1_1") (pintype "passive"))
      (node (ref "SV3") (pin "2") (pinfunction "2_2") (pintype "passive"))
    )
    (net (code "159") (name "SOUT1") (class "Default")
      (node (ref "IC1") (pin "28") (pinfunction "SOUT_28") (pintype "bidirectional"))
      (node (ref "R2") (pin "1") (pinfunction "1_1") (pintype "passive"))
      (node (ref "SV1") (pin "1") (pinfunction "1_1") (pintype "passive"))
    )
    (net (code "160") (name "SOUT2") (class "Default")
      (node (ref "IC2") (pin "28") (pinfunction "SOUT_28") (pintype "bidirectional"))
      (node (ref "R7") (pin "1") (pinfunction "1_1") (pintype "passive"))
      (node (ref "SV2") (pin "1") (pinfunction "1_1") (pintype "passive"))
    )
    (net (code "161") (name "SOUT3") (class "Default")
      (node (ref "IC3") (pin "28") (pinfunction "SOUT_28") (pintype "bidirectional"))
      (node (ref "R12") (pin "1") (pinfunction "1_1") (pintype "passive"))
      (node (ref "SV3") (pin "1") (pinfunction "1_1") (pintype "passive"))
    )
    (net (code "162") (name "unconnected-(R1-Pad2)") (class "Default")
      (node (ref "R1") (pin "2") (pinfunction "2_2") (pintype "passive"))
    )
    (net (code "163") (name "unconnected-(R2-Pad2)") (class "Default")
      (node (ref "R2") (pin "2") (pinfunction "2_2") (pintype "passive"))
    )
    (net (code "164") (name "unconnected-(R3-Pad2)") (class "Default")
      (node (ref "R3") (pin "2") (pinfunction "2_2") (pintype "passive"))
    )
    (net (code "165") (name "unconnected-(R4-Pad2)") (class "Default")
      (node (ref "R4") (pin "2") (pinfunction "2_2") (pintype "passive"))
    )
    (net (code "166") (name "unconnected-(R5-Pad2)") (class "Default")
      (node (ref "R5") (pin "2") (pinfunction "2_2") (pintype "passive"))
    )
    (net (code "167") (name "unconnected-(R6-Pad2)") (class "Default")
      (node (ref "R6") (pin "2") (pinfunction "2_2") (pintype "passive"))
    )
    (net (code "168") (name "unconnected-(R7-Pad2)") (class "Default")
      (node (ref "R7") (pin "2") (pinfunction "2_2") (pintype "passive"))
    )
    (net (code "169") (name "unconnected-(R8-Pad2)") (class "Default")
      (node (ref "R8") (pin "2") (pinfunction "2_2") (pintype "passive"))
    )
    (net (code "170") (name "unconnected-(R9-Pad2)") (class "Default")
      (node (ref "R9") (pin "2") (pinfunction "2_2") (pintype "passive"))
    )
    (net (code "171") (name "unconnected-(R10-Pad2)") (class "Default")
      (node (ref "R10") (pin "2") (pinfunction "2_2") (pintype "passive"))
    )
    (net (code "172") (name "unconnected-(R11-Pad2)") (class "Default")
      (node (ref "R11") (pin "2") (pinfunction "2_2") (pintype "passive"))
    )
    (net (code "173") (name "unconnected-(R12-Pad2)") (class "Default")
      (node (ref "R12") (pin "2") (pinfunction "2_2") (pintype "passive"))
    )
    (net (code "174") (name "unconnected-(R13-Pad2)") (class "Default")
      (node (ref "R13") (pin "2") (pinfunction "2_2") (pintype "passive"))
    )
    (net (code "175") (name "unconnected-(R14-Pad2)") (class "Default")
      (node (ref "R14") (pin "2") (pinfunction "2_2") (pintype "passive"))
    )
    (net (code "176") (name "unconnected-(R15-Pad2)") (class "Default")
      (node (ref "R15") (pin "2") (pinfunction "2_2") (pintype "passive"))
    )
    (net (code "177") (name "unconnected-(R16-Pad2)") (class "Default")
      (node (ref "R16") (pin "2") (pinfunction "2_2") (pintype "passive"))
    )
    (net (code "178") (name "unconnected-(R17-Pad2)") (class "Default")
      (node (ref "R17") (pin "2") (pinfunction "2_2") (pintype "passive"))
    )
    (net (code "179") (name "unconnected-(R18-Pad2)") (class "Default")
      (node (ref "R18") (pin "2") (pinfunction "2_2") (pintype "passive"))
    )
    (net (code "180") (name "unconnected-(SV1-Pad3)") (class "Default")
      (node (ref "SV1") (pin "3") (pinfunction "3_3") (pintype "passive"))
    )
    (net (code "181") (name "unconnected-(SV1-Pad4)") (class "Default")
      (node (ref "SV1") (pin "4") (pinfunction "4_4") (pintype "passive"))
    )
    (net (code "182") (name "unconnected-(SV1-Pad5)") (class "Default")
      (node (ref "SV1") (pin "5") (pinfunction "5_5") (pintype "passive"))
    )
    (net (code "183") (name "unconnected-(SV2-Pad3)") (class "Default")
      (node (ref "SV2") (pin "3") (pinfunction "3_3") (pintype "passive"))
    )
    (net (code "184") (name "unconnected-(SV2-Pad4)") (class "Default")
      (node (ref "SV2") (pin "4") (pinfunction "4_4") (pintype "passive"))
    )
    (net (code "185") (name "unconnected-(SV2-Pad5)") (class "Default")
      (node (ref "SV2") (pin "5") (pinfunction "5_5") (pintype "passive"))
    )
    (net (code "186") (name "unconnected-(SV3-Pad3)") (class "Default")
      (node (ref "SV3") (pin "3") (pinfunction "3_3") (pintype "passive"))
    )
    (net (code "187") (name "unconnected-(SV3-Pad4)") (class "Default")
      (node (ref "SV3") (pin "4") (pinfunction "4_4") (pintype "passive"))
    )
    (net (code "188") (name "unconnected-(SV3-Pad5)") (class "Default")
      (node (ref "SV3") (pin "5") (pinfunction "5_5") (pintype "passive"))
    )
  )
)
